# LED_v0_1_2.net
KiCad netlist of a schematic drawn in EAGLE
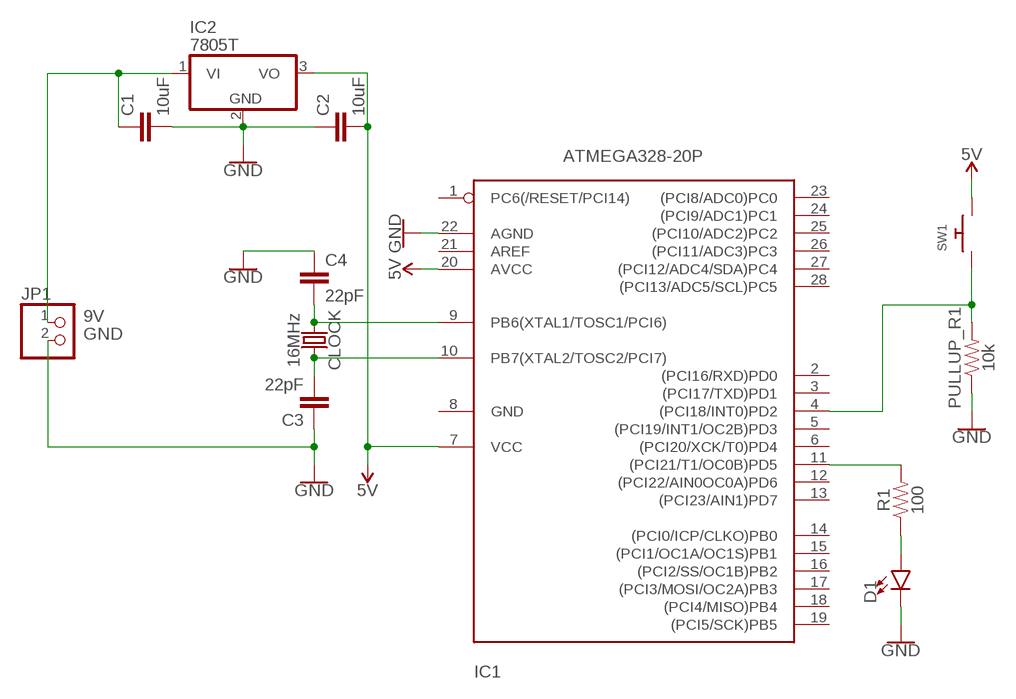
[diagram p0: schematic, sheet 1]

(export (version "E")
  (design (tool "Eeschema 10.0.6"))
  (components
    (comp (ref "C1")
      (value "10uF")
      (footprint "eagle-import:1210")
      (libsource (lib "eagle-import") (part "10UF-1210-50V-20%"))
    )
    (comp (ref "C2")
      (value "10uF")
      (footprint "eagle-import:1210")
      (libsource (lib "eagle-import") (part "10UF-1210-50V-20%"))
    )
    (comp (ref "C3")
      (value "22pF")
      (footprint "eagle-import:0603")
      (libsource (lib "eagle-import") (part "22PF-0603-50V-5%"))
    )
    (comp (ref "C4")
      (value "22pF")
      (footprint "eagle-import:0603")
      (libsource (lib "eagle-import") (part "22PF-0603-50V-5%"))
    )
    (comp (ref "CLOCK")
      (value "16MHz")
      (footprint "eagle-import:HC49US")
      (libsource (lib "eagle-import") (part "CRYSTAL-16MHZPTH-HC49US"))
    )
    (comp (ref "D1")
      (value "LED5MM")
      (footprint "eagle-import:LED_5MM")
      (libsource (lib "eagle-import") (part "LED5MM"))
    )
    (comp (ref "IC1")
      (value "ATMEGA328-20P")
      (footprint "eagle-import:DIL28-3")
      (libsource (lib "eagle-import") (part "ATMEGA328P-20"))
    )
    (comp (ref "IC2")
      (value "7805T")
      (footprint "eagle-import:TO220H")
      (libsource (lib "eagle-import") (part "78T05"))
    )
    (comp (ref "JP1")
      (value "PINHD-1X2")
      (footprint "eagle-import:1X02")
      (libsource (lib "eagle-import") (part "PINHD-1X2"))
    )
    (comp (ref "PULLUP_R1")
      (value "10k")
      (footprint "eagle-import:AXIAL-0.3")
      (libsource (lib "eagle-import") (part "10KOHM-HORIZ-1/4W-1%"))
    )
    (comp (ref "R1")
      (value "100")
      (footprint "eagle-import:AXIAL-0.3")
      (libsource (lib "eagle-import") (part "100OHM-HORIZ-1/4W-1%"))
    )
    (comp (ref "SW1")
      (value "SWITCH_PUSHBUTTONEVQ-PE")
      (footprint "eagle-import:TACT_PANA-EVQ")
      (libsource (lib "eagle-import") (part "SWITCH_PUSHBUTTONEVQ-PE"))
    )
  )
  (nets
    (net (code "1") (name "/9V") (class "Default")
      (node (ref "C1") (pin "1") (pinfunction "1_1") (pintype "passive"))
      (node (ref "IC2") (pin "1") (pinfunction "VI_1") (pintype "input"))
      (node (ref "JP1") (pin "1") (pinfunction "1_1") (pintype "passive"))
    )
    (net (code "2") (name "5V") (class "Default")
      (node (ref "C2") (pin "2") (pinfunction "2_2") (pintype "passive"))
      (node (ref "IC1") (pin "20") (pinfunction "AVCC_20") (pintype "bidirectional"))
      (node (ref "IC1") (pin "7") (pinfunction "VCC_7") (pintype "bidirectional"))
      (node (ref "IC2") (pin "3") (pinfunction "VO_3") (pintype "passive"))
      (node (ref "SW1") (pin "P$2") (pinfunction "P$2_P$2") (pintype "passive"))
    )
    (net (code "3") (name "GND") (class "Default")
      (node (ref "C1") (pin "2") (pinfunction "2_2") (pintype "passive"))
      (node (ref "C2") (pin "1") (pinfunction "1_1") (pintype "passive"))
      (node (ref "C3") (pin "1") (pinfunction "1_1") (pintype "passive"))
      (node (ref "C4") (pin "1") (pinfunction "1_1") (pintype "passive"))
      (node (ref "D1") (pin "K") (pinfunction "C_K") (pintype "passive"))
      (node (ref "IC1") (pin "22") (pinfunction "AGND_22") (pintype "bidirectional"))
      (node (ref "IC2") (pin "2") (pinfunction "GND_2") (pintype "passive"))
      (node (ref "JP1") (pin "2") (pinfunction "2_2") (pintype "passive"))
      (node (ref "PULLUP_R1") (pin "P$1") (pinfunction "1_P$1") (pintype "passive"))
    )
    (net (code "4") (name "Net-(IC1-(PCI18{slash}INT0)PD2)") (class "Default")
      (node (ref "IC1") (pin "4") (pinfunction "(PCI18/INT0)PD2_4") (pintype "bidirectional"))
      (node (ref "PULLUP_R1") (pin "P$2") (pinfunction "2_P$2") (pintype "passive"))
      (node (ref "SW1") (pin "P$1") (pinfunction "P$1_P$1") (pintype "passive"))
    )
    (net (code "5") (name "Net-(IC1-(PCI21{slash}T1{slash}OC0B)PD5)") (class "Default")
      (node (ref "IC1") (pin "11") (pinfunction "(PCI21/T1/OC0B)PD5_11") (pintype "bidirectional"))
      (node (ref "R1") (pin "P$2") (pinfunction "2_P$2") (pintype "passive"))
    )
    (net (code "6") (name "Net-(IC1-PB6(XTAL1{slash}TOSC1{slash}PCI6))") (class "Default")
      (node (ref "C4") (pin "2") (pinfunction "2_2") (pintype "passive"))
      (node (ref "CLOCK") (pin "1") (pinfunction "1_1") (pintype "passive"))
      (node (ref "IC1") (pin "9") (pinfunction "PB6(XTAL1/TOSC1/PCI6)_9") (pintype "bidirectional"))
    )
    (net (code "7") (name "Net-(IC1-PB7(XTAL2{slash}TOSC2{slash}PCI7))") (class "Default")
      (node (ref "C3") (pin "2") (pinfunction "2_2") (pintype "passive"))
      (node (ref "CLOCK") (pin "2") (pinfunction "2_2") (pintype "passive"))
      (node (ref "IC1") (pin "10") (pinfunction "PB7(XTAL2/TOSC2/PCI7)_10") (pintype "bidirectional"))
    )
    (net (code "8") (name "Net-(R1-1)") (class "Default")
      (node (ref "D1") (pin "A") (pinfunction "A_A") (pintype "passive"))
      (node (ref "R1") (pin "P$1") (pinfunction "1_P$1") (pintype "passive"))
    )
    (net (code "9") (name "unconnected-(IC1-(PCI0{slash}ICP{slash}CLKO)PB0-Pad14)") (class "Default")
      (node (ref "IC1") (pin "14") (pinfunction "(PCI0/ICP/CLKO)PB0_14") (pintype "bidirectional"))
    )
    (net (code "10") (name "unconnected-(IC1-(PCI1{slash}OC1A{slash}OC1S)PB1-Pad15)") (class "Default")
      (node (ref "IC1") (pin "15") (pinfunction "(PCI1/OC1A/OC1S)PB1_15") (pintype "bidirectional"))
    )
    (net (code "11") (name "unconnected-(IC1-(PCI2{slash}SS{slash}OC1B)PB2-Pad16)") (class "Default")
      (node (ref "IC1") (pin "16") (pinfunction "(PCI2/SS/OC1B)PB2_16") (pintype "bidirectional"))
    )
    (net (code "12") (name "unconnected-(IC1-(PCI3{slash}MOSI{slash}OC2A)PB3-Pad17)") (class "Default")
      (node (ref "IC1") (pin "17") (pinfunction "(PCI3/MOSI/OC2A)PB3_17") (pintype "bidirectional"))
    )
    (net (code "13") (name "unconnected-(IC1-(PCI4{slash}MISO)PB4-Pad18)") (class "Default")
      (node (ref "IC1") (pin "18") (pinfunction "(PCI4/MISO)PB4_18") (pintype "bidirectional"))
    )
    (net (code "14") (name "unconnected-(IC1-(PCI5{slash}SCK)PB5-Pad19)") (class "Default")
      (node (ref "IC1") (pin "19") (pinfunction "(PCI5/SCK)PB5_19") (pintype "bidirectional"))
    )
    (net (code "15") (name "unconnected-(IC1-(PCI8{slash}ADC0)PC0-Pad23)") (class "Default")
      (node (ref "IC1") (pin "23") (pinfunction "(PCI8/ADC0)PC0_23") (pintype "bidirectional"))
    )
    (net (code "16") (name "unconnected-(IC1-(PCI9{slash}ADC1)PC1-Pad24)") (class "Default")
      (node (ref "IC1") (pin "24") (pinfunction "(PCI9/ADC1)PC1_24") (pintype "bidirectional"))
    )
    (net (code "17") (name "unconnected-(IC1-(PCI10{slash}ADC2)PC2-Pad25)") (class "Default")
      (node (ref "IC1") (pin "25") (pinfunction "(PCI10/ADC2)PC2_25") (pintype "bidirectional"))
    )
    (net (code "18") (name "unconnected-(IC1-(PCI11{slash}ADC3)PC3-Pad26)") (class "Default")
      (node (ref "IC1") (pin "26") (pinfunction "(PCI11/ADC3)PC3_26") (pintype "bidirectional"))
    )
    (net (code "19") (name "unconnected-(IC1-(PCI12{slash}ADC4{slash}SDA)PC4-Pad27)") (class "Default")
      (node (ref "IC1") (pin "27") (pinfunction "(PCI12/ADC4/SDA)PC4_27") (pintype "bidirectional"))
    )
    (net (code "20") (name "unconnected-(IC1-(PCI13{slash}ADC5{slash}SCL)PC5-Pad28)") (class "Default")
      (node (ref "IC1") (pin "28") (pinfunction "(PCI13/ADC5/SCL)PC5_28") (pintype "bidirectional"))
    )
    (net (code "21") (name "unconnected-(IC1-(PCI16{slash}RXD)PD0-Pad2)") (class "Default")
      (node (ref "IC1") (pin "2") (pinfunction "(PCI16/RXD)PD0_2") (pintype "bidirectional"))
    )
    (net (code "22") (name "unconnected-(IC1-(PCI17{slash}TXD)PD1-Pad3)") (class "Default")
      (node (ref "IC1") (pin "3") (pinfunction "(PCI17/TXD)PD1_3") (pintype "bidirectional"))
    )
    (net (code "23") (name "unconnected-(IC1-(PCI19{slash}INT1{slash}OC2B)PD3-Pad5)") (class "Default")
      (node (ref "IC1") (pin "5") (pinfunction "(PCI19/INT1/OC2B)PD3_5") (pintype "bidirectional"))
    )
    (net (code "24") (name "unconnected-(IC1-(PCI20{slash}XCK{slash}T0)PD4-Pad6)") (class "Default")
      (node (ref "IC1") (pin "6") (pinfunction "(PCI20/XCK/T0)PD4_6") (pintype "bidirectional"))
    )
    (net (code "25") (name "unconnected-(IC1-(PCI22{slash}AIN0OC0A)PD6-Pad12)") (class "Default")
      (node (ref "IC1") (pin "12") (pinfunction "(PCI22/AIN0OC0A)PD6_12") (pintype "bidirectional"))
    )
    (net (code "26") (name "unconnected-(IC1-(PCI23{slash}AIN1)PD7-Pad13)") (class "Default")
      (node (ref "IC1") (pin "13") (pinfunction "(PCI23/AIN1)PD7_13") (pintype "bidirectional"))
    )
    (net (code "27") (name "unconnected-(IC1-AREF-Pad21)") (class "Default")
      (node (ref "IC1") (pin "21") (pinfunction "AREF_21") (pintype "bidirectional"))
    )
    (net (code "28") (name "unconnected-(IC1-GND-Pad8)") (class "Default")
      (node (ref "IC1") (pin "8") (pinfunction "GND_8") (pintype "bidirectional"))
    )
    (net (code "29") (name "unconnected-(IC1-PC6({slash}RESET{slash}PCI14)-Pad1)") (class "Default")
      (node (ref "IC1") (pin "1") (pinfunction "PC6(/RESET/PCI14)_1") (pintype "bidirectional"))
    )
  )
)
